# femtoBeacon_PRO_r3_0_1_single_sided.net
KiCad netlist of a schematic drawn in EAGLE
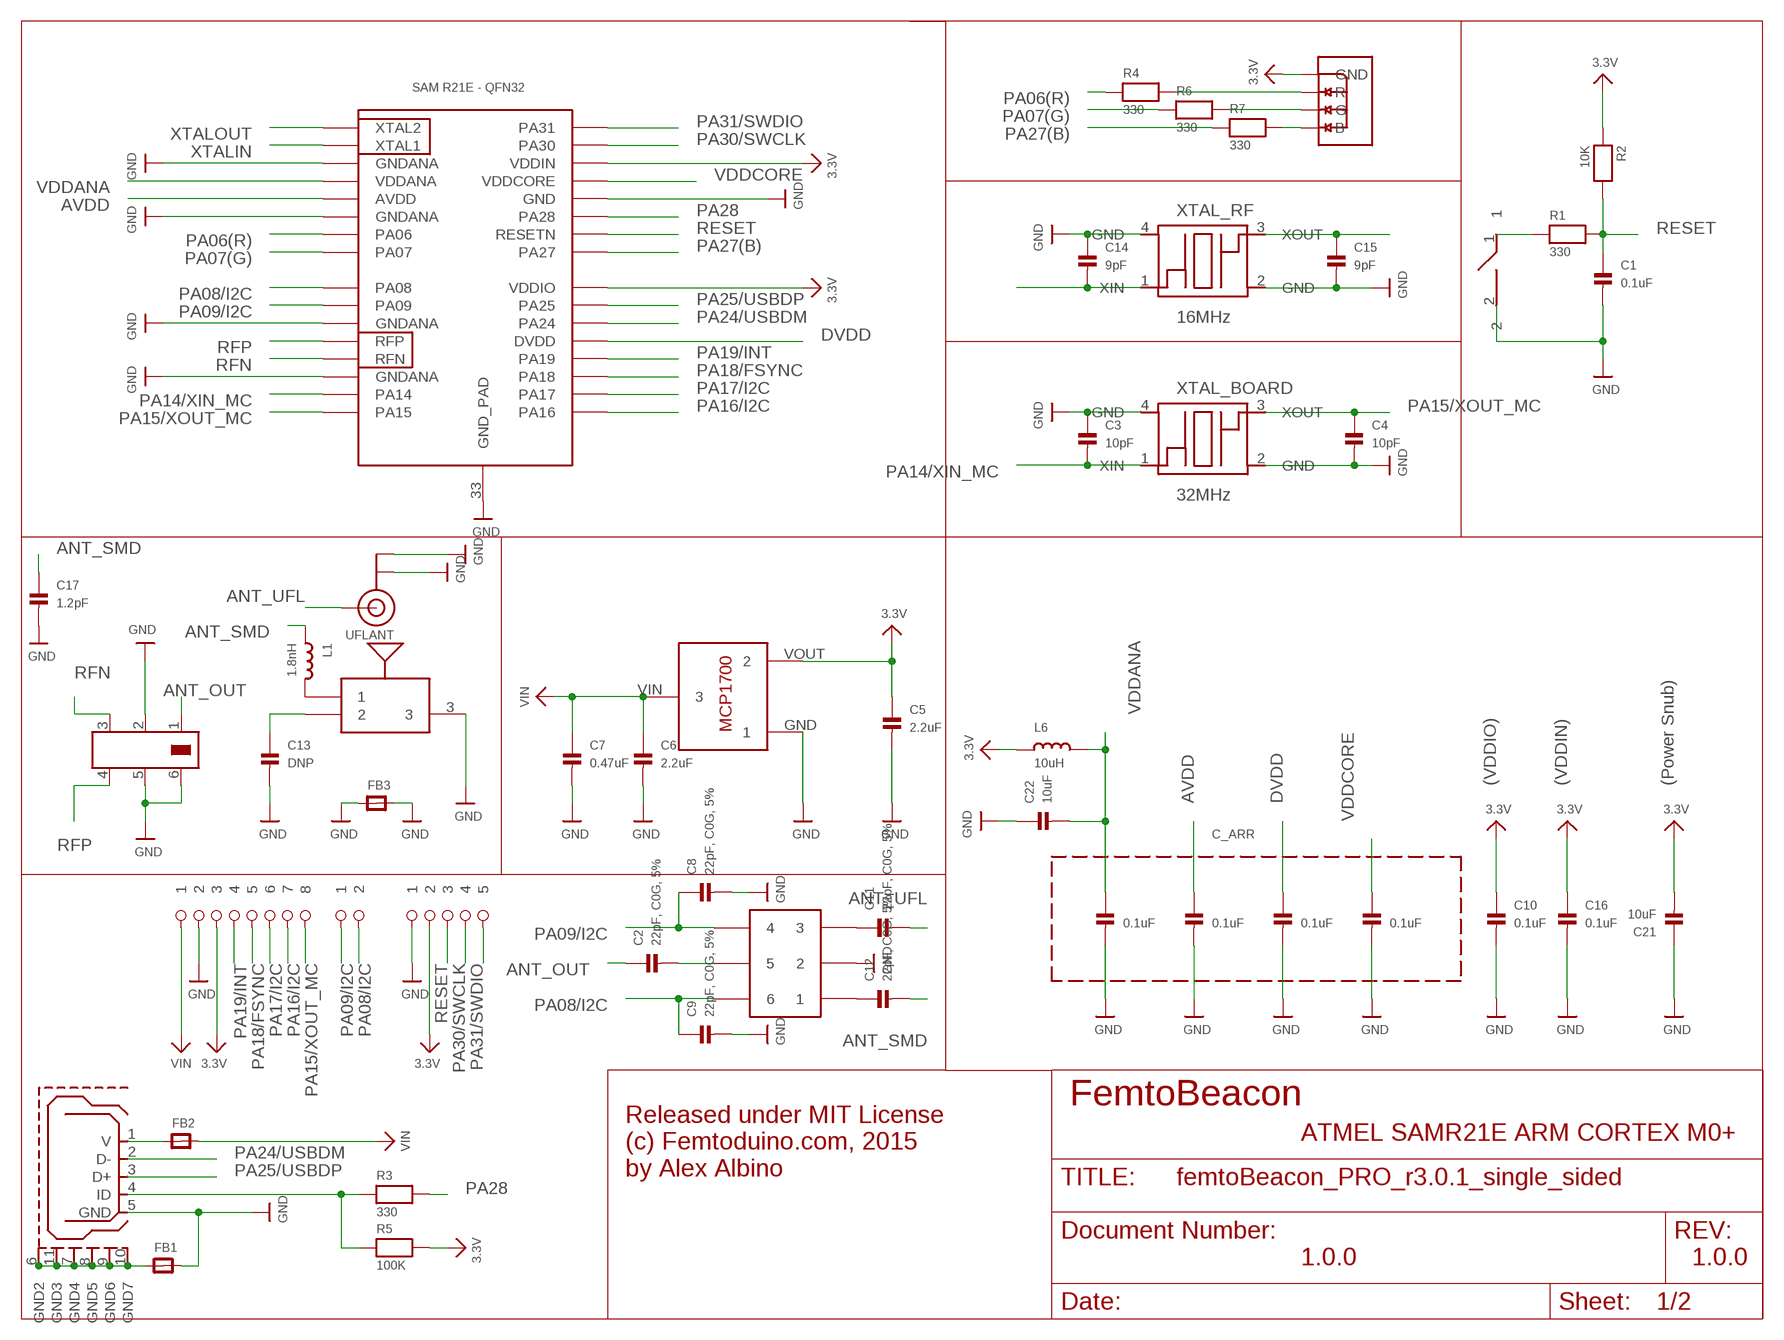
[diagram p0: schematic, sheet 1]
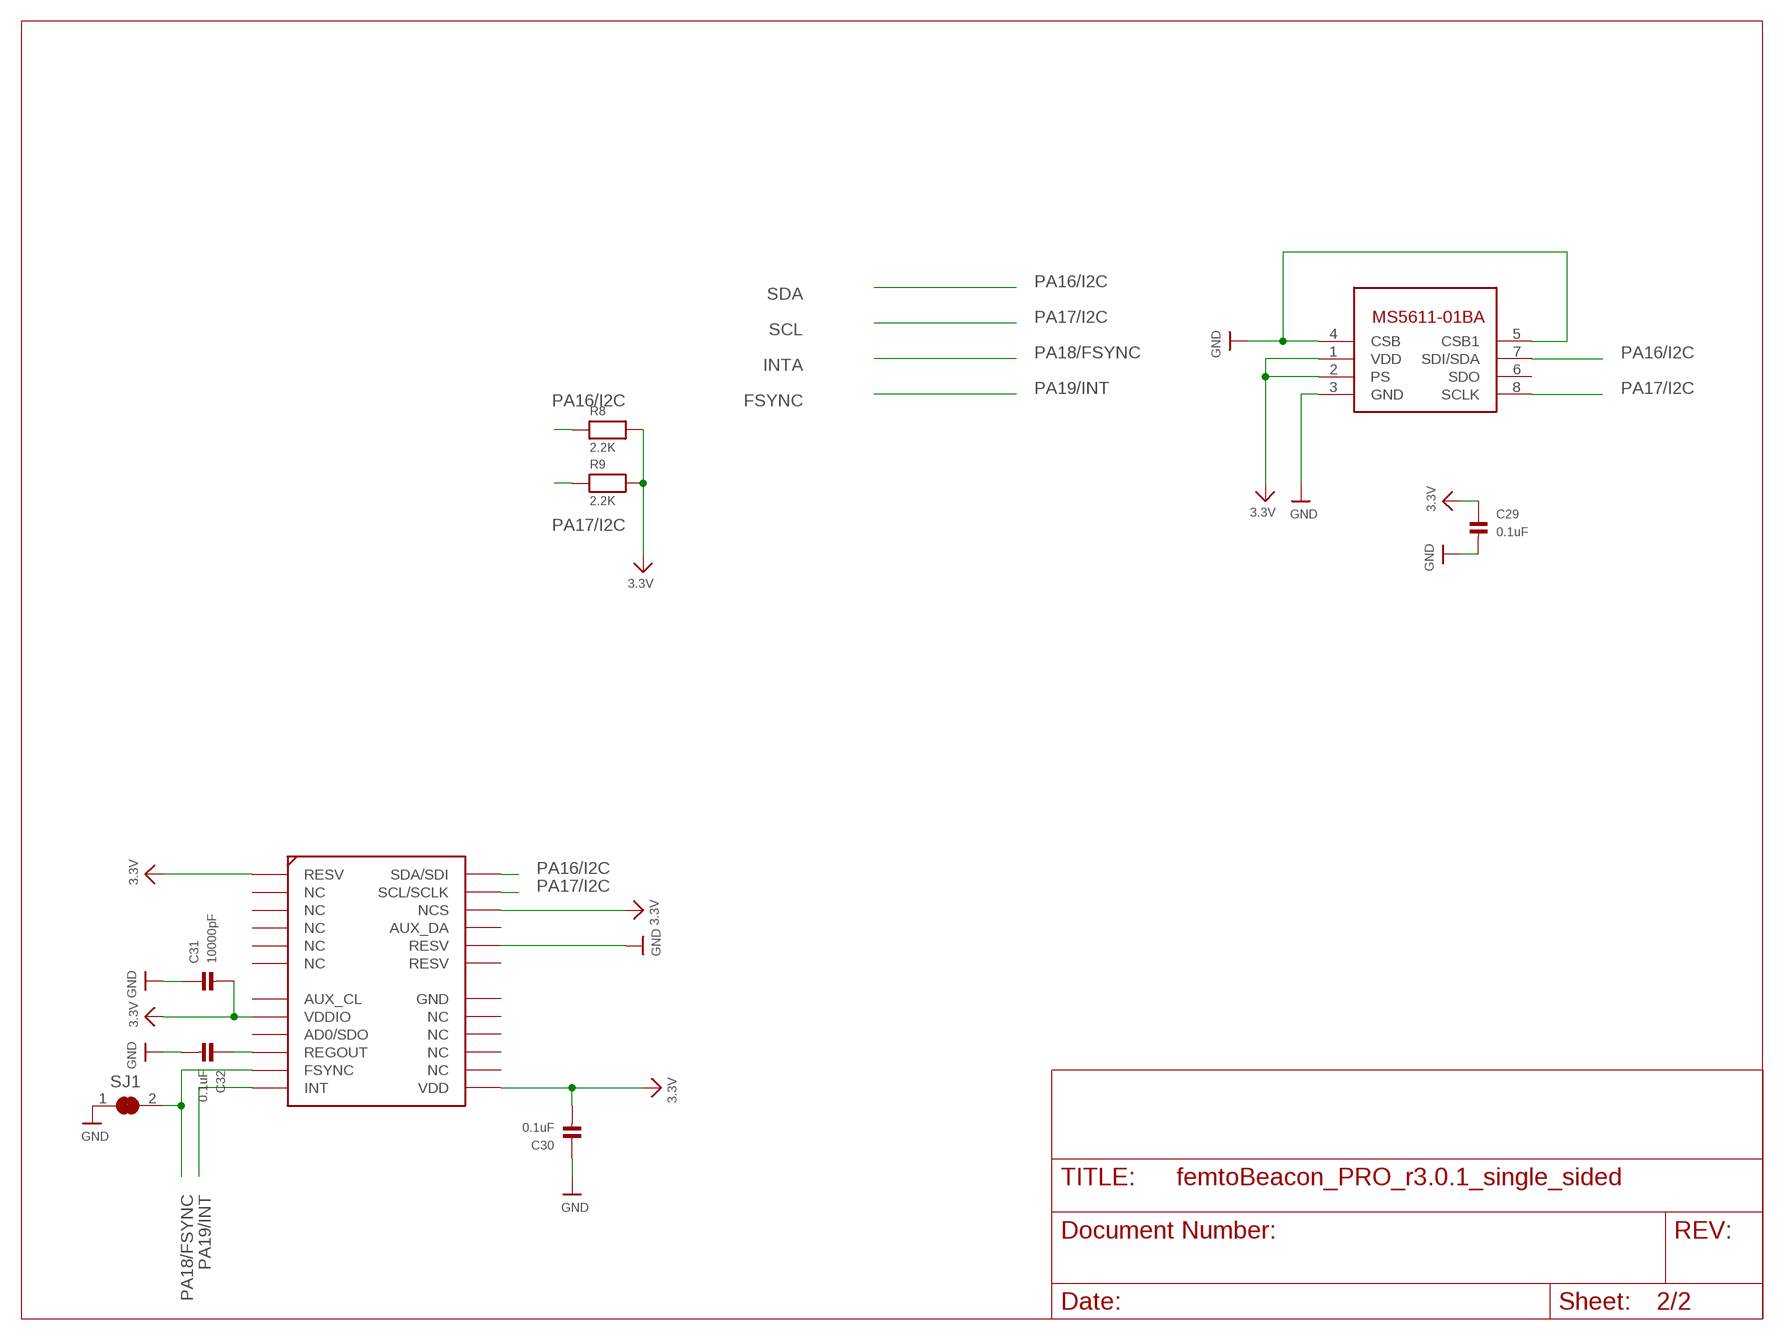
[diagram p1: schematic, sheet 2]

(export (version "E")
  (design (tool "Eeschema 10.0.6"))
  (components
    (comp (ref "BARO")
      (value "MS5611-01BA03")
      (footprint "eagle-import:MS5611-01BA03")
      (libsource (lib "eagle-import") (part "MS5611-01BA03"))
    )
    (comp (ref "C29")
      (value "0.1uF")
      (footprint "eagle-import:_0402MP")
      (fields (field (name "DIGIKEY_PART") "490-3194-1-ND"))
      (libsource (lib "eagle-import") (part "CAP_CERAMIC_0402MP"))
    )
    (comp (ref "C30")
      (value "0.1uF")
      (footprint "eagle-import:_0402MP")
      (fields (field (name "DIGIKEY_PART") "490-3194-1-ND"))
      (libsource (lib "eagle-import") (part "CAP_CERAMIC_0402MP"))
    )
    (comp (ref "C31")
      (value "10000pF")
      (footprint "eagle-import:_0402MP")
      (fields (field (name "DIGIKEY_PART") "490-3194-1-ND"))
      (libsource (lib "eagle-import") (part "CAP_CERAMIC_0402MP"))
    )
    (comp (ref "C32")
      (value "0.1uF")
      (footprint "eagle-import:_0402MP")
      (fields (field (name "DIGIKEY_PART") "490-3194-1-ND"))
      (libsource (lib "eagle-import") (part "CAP_CERAMIC_0402MP"))
    )
    (comp (ref "IMU")
      (value "MPU-9250")
      (footprint "eagle-import:QFN_3X3MM")
      (libsource (lib "eagle-import") (part "MPU-9250"))
    )
    (comp (ref "R8")
      (value "2.2K")
      (footprint "eagle-import:_0402MP")
      (libsource (lib "eagle-import") (part "RESISTOR_0402MP"))
    )
    (comp (ref "R9")
      (value "2.2K")
      (footprint "eagle-import:_0402MP")
      (libsource (lib "eagle-import") (part "RESISTOR_0402MP"))
    )
    (comp (ref "SJ1")
      (value "SOLDERJUMPER_CLOSED")
      (footprint "eagle-import:SOLDERJUMPER_CLOSEDWIRE")
      (libsource (lib "eagle-import") (part "SOLDERJUMPER_CLOSED"))
    )
    (comp (ref "ASWITCH")
      (value "AS222-92LF")
      (footprint "eagle-import:AS222-92LF")
      (libsource (lib "eagle-import") (part "AS222-92LF"))
    )
    (comp (ref "BALUN")
      (value "JOHANSON_2450BM15A0015E")
      (footprint "eagle-import:0805_BALUN")
      (libsource (lib "eagle-import") (part "JOHANSON_2450BM15A0015E"))
    )
    (comp (ref "BTN_RESET")
      (value "DNP")
      (footprint "eagle-import:SPST_SMD")
      (libsource (lib "eagle-import") (part "SPST_SMD"))
    )
    (comp (ref "C1")
      (value "0.1uF")
      (footprint "eagle-import:_0402MP")
      (fields (field (name "DIGIKEY_PART") "490-3194-1-ND"))
      (libsource (lib "eagle-import") (part "CAP_CERAMIC_0402MP"))
    )
    (comp (ref "C2")
      (value "22pF, C0G, 5%")
      (footprint "eagle-import:_0402MP")
      (fields (field (name "DIGIKEY_PART") "490-3194-1-ND"))
      (libsource (lib "eagle-import") (part "CAP_CERAMIC_0402MP"))
    )
    (comp (ref "C3")
      (value "10pF")
      (footprint "eagle-import:_0402MP")
      (fields (field (name "DIGIKEY_PART") "490-3194-1-ND"))
      (libsource (lib "eagle-import") (part "CAP_CERAMIC_0402MP"))
    )
    (comp (ref "C4")
      (value "10pF")
      (footprint "eagle-import:_0402MP")
      (fields (field (name "DIGIKEY_PART") "490-3194-1-ND"))
      (libsource (lib "eagle-import") (part "CAP_CERAMIC_0402MP"))
    )
    (comp (ref "C5")
      (value "2.2uF")
      (footprint "eagle-import:_0402MP")
      (libsource (lib "eagle-import") (part "CAP_CERAMIC_0402MP"))
    )
    (comp (ref "C6")
      (value "2.2uF")
      (footprint "eagle-import:_0402MP")
      (libsource (lib "eagle-import") (part "CAP_CERAMIC_0402MP"))
    )
    (comp (ref "C7")
      (value "0.47uF")
      (footprint "eagle-import:_0402MP")
      (libsource (lib "eagle-import") (part "CAP_CERAMIC_0402MP"))
    )
    (comp (ref "C8")
      (value "22pF, C0G, 5%")
      (footprint "eagle-import:_0402MP")
      (fields (field (name "DIGIKEY_PART") "490-3194-1-ND"))
      (libsource (lib "eagle-import") (part "CAP_CERAMIC_0402MP"))
    )
    (comp (ref "C9")
      (value "22pF, C0G, 5%")
      (footprint "eagle-import:_0402MP")
      (fields (field (name "DIGIKEY_PART") "490-3194-1-ND"))
      (libsource (lib "eagle-import") (part "CAP_CERAMIC_0402MP"))
    )
    (comp (ref "C10")
      (value "0.1uF")
      (footprint "eagle-import:_0402MP")
      (fields (field (name "DIGIKEY_PART") "490-3194-1-ND"))
      (libsource (lib "eagle-import") (part "CAP_CERAMIC_0402MP"))
    )
    (comp (ref "C11")
      (value "22pF, C0G, 5%")
      (footprint "eagle-import:_0402MP")
      (fields (field (name "DIGIKEY_PART") "490-3194-1-ND"))
      (libsource (lib "eagle-import") (part "CAP_CERAMIC_0402MP"))
    )
    (comp (ref "C12")
      (value "22pF, C0G, 5%")
      (footprint "eagle-import:_0402MP")
      (fields (field (name "DIGIKEY_PART") "490-3194-1-ND"))
      (libsource (lib "eagle-import") (part "CAP_CERAMIC_0402MP"))
    )
    (comp (ref "C13")
      (value "DNP")
      (footprint "eagle-import:_0402MP")
      (fields (field (name "DIGIKEY_PART") "490-3194-1-ND"))
      (libsource (lib "eagle-import") (part "CAP_CERAMIC_0402MP"))
    )
    (comp (ref "C14")
      (value "9pF")
      (footprint "eagle-import:_0402MP")
      (fields (field (name "DIGIKEY_PART") "490-3194-1-ND"))
      (libsource (lib "eagle-import") (part "CAP_CERAMIC_0402MP"))
    )
    (comp (ref "C15")
      (value "9pF")
      (footprint "eagle-import:_0402MP")
      (fields (field (name "DIGIKEY_PART") "490-3194-1-ND"))
      (libsource (lib "eagle-import") (part "CAP_CERAMIC_0402MP"))
    )
    (comp (ref "C16")
      (value "0.1uF")
      (footprint "eagle-import:_0402MP")
      (fields (field (name "DIGIKEY_PART") "490-3194-1-ND"))
      (libsource (lib "eagle-import") (part "CAP_CERAMIC_0402MP"))
    )
    (comp (ref "C17")
      (value "1.2pF")
      (footprint "eagle-import:_0402MP")
      (libsource (lib "eagle-import") (part "CAP_CERAMIC_0402MP"))
    )
    (comp (ref "C21")
      (value "10uF")
      (footprint "eagle-import:_0402MP")
      (libsource (lib "eagle-import") (part "CAP_CERAMIC_0402MP"))
    )
    (comp (ref "C22")
      (value "10uF")
      (footprint "eagle-import:_0402MP")
      (libsource (lib "eagle-import") (part "CAP_CERAMIC_0402MP"))
    )
    (comp (ref "C_ARR")
      (value "0.1uF")
      (footprint "eagle-import:CAPACITOR_ARRAY_1206_MONO_1X4")
      (libsource (lib "eagle-import") (part "KEMET_CERAMIC_CAPACITOR_ARRAY_1X4"))
    )
    (comp (ref "FB1")
      (value "FERRITE_0603MP")
      (footprint "eagle-import:_0603MP")
      (libsource (lib "eagle-import") (part "FERRITE_0603MP"))
    )
    (comp (ref "FB2")
      (value "FERRITE_0603MP")
      (footprint "eagle-import:_0603MP")
      (libsource (lib "eagle-import") (part "FERRITE_0603MP"))
    )
    (comp (ref "FB3")
      (value "FERRITE_0603MP")
      (footprint "eagle-import:_0603MP")
      (libsource (lib "eagle-import") (part "FERRITE_0603MP"))
    )
    (comp (ref "IC")
      (value "ATSAMR21E18A-MUT")
      (footprint "eagle-import:QFN32")
      (libsource (lib "eagle-import") (part "ATSAMR21E18A-MUT"))
    )
    (comp (ref "L1")
      (value "1.8nH")
      (footprint "eagle-import:_0603MP")
      (libsource (lib "eagle-import") (part "INDUCTOR_0603MP"))
    )
    (comp (ref "L6")
      (value "10uH")
      (footprint "eagle-import:_0603MP")
      (libsource (lib "eagle-import") (part "INDUCTOR_0603MP"))
    )
    (comp (ref "LDO_VREG")
      (value "MCP1700T-3302E/TT")
      (footprint "eagle-import:MCP1700T-3302E_TT")
      (libsource (lib "eagle-import") (part "MCP1700T-3302E/TT"))
    )
    (comp (ref "R1")
      (value "330")
      (footprint "eagle-import:_0402MP")
      (libsource (lib "eagle-import") (part "RESISTOR_0402MP"))
    )
    (comp (ref "R2")
      (value "10K")
      (footprint "eagle-import:_0402MP")
      (libsource (lib "eagle-import") (part "RESISTOR_0402MP"))
    )
    (comp (ref "R3")
      (value "330")
      (footprint "eagle-import:_0402MP")
      (libsource (lib "eagle-import") (part "RESISTOR_0402MP"))
    )
    (comp (ref "R4")
      (value "330")
      (footprint "eagle-import:_0402MP")
      (libsource (lib "eagle-import") (part "RESISTOR_0402MP"))
    )
    (comp (ref "R5")
      (value "100K")
      (footprint "eagle-import:_0402MP")
      (libsource (lib "eagle-import") (part "RESISTOR_0402MP"))
    )
    (comp (ref "R6")
      (value "330")
      (footprint "eagle-import:_0402MP")
      (libsource (lib "eagle-import") (part "RESISTOR_0402MP"))
    )
    (comp (ref "R7")
      (value "330")
      (footprint "eagle-import:_0402MP")
      (libsource (lib "eagle-import") (part "RESISTOR_0402MP"))
    )
    (comp (ref "RGBLED")
      (value "LRTB_R48G")
      (footprint "eagle-import:LRTB_R48G")
      (libsource (lib "eagle-import") (part "LRTB_R48G"))
    )
    (comp (ref "SMDANT")
      (value "PULSE_ANT_2.4GHZ")
      (footprint "eagle-import:ANT_BAR")
      (libsource (lib "eagle-import") (part "PULSE_ANT_2.4GHZ"))
    )
    (comp (ref "U$5")
      (value "1X8_ROUND")
      (footprint "eagle-import:1X8_ROUND")
      (libsource (lib "eagle-import") (part "1X8_ROUND"))
    )
    (comp (ref "U$9")
      (value "1X2_ROUND")
      (footprint "eagle-import:1X2_ROUND")
      (libsource (lib "eagle-import") (part "1X2_ROUND"))
    )
    (comp (ref "U$10")
      (value "1X5_ROUND")
      (footprint "eagle-import:1X5_ROUND")
      (libsource (lib "eagle-import") (part "1X5_ROUND"))
    )
    (comp (ref "UFLANT")
      (value "ANTENNA_U.FL")
      (footprint "eagle-import:U.FL")
      (libsource (lib "eagle-import") (part "ANTENNA_U.FL"))
    )
    (comp (ref "USB")
      (value "USB_MICROB")
      (footprint "eagle-import:USB_MICROB_PACKAGE")
      (libsource (lib "eagle-import") (part "USB_MICROB"))
    )
    (comp (ref "XTAL_BOARD")
      (value "32MHz")
      (footprint "eagle-import:FA-128")
      (libsource (lib "eagle-import") (part "FA-128"))
    )
    (comp (ref "XTAL_RF")
      (value "16MHz")
      (footprint "eagle-import:TSX-3225")
      (libsource (lib "eagle-import") (part "TSX-3225"))
    )
  )
  (nets
    (net (code "1") (name "3.3V") (class "Default")
      (node (ref "BARO") (pin "1") (pinfunction "VDD_1") (pintype "bidirectional"))
      (node (ref "BARO") (pin "2") (pinfunction "PS_2") (pintype "bidirectional"))
      (node (ref "C10") (pin "1") (pinfunction "P$1_1") (pintype "passive"))
      (node (ref "C16") (pin "1") (pinfunction "P$1_1") (pintype "passive"))
      (node (ref "C21") (pin "2") (pinfunction "P$2_2") (pintype "passive"))
      (node (ref "C29") (pin "1") (pinfunction "P$1_1") (pintype "passive"))
      (node (ref "C30") (pin "2") (pinfunction "P$2_2") (pintype "passive"))
      (node (ref "C31") (pin "2") (pinfunction "P$2_2") (pintype "passive"))
      (node (ref "C5") (pin "1") (pinfunction "P$1_1") (pintype "passive"))
      (node (ref "IC") (pin "24") (pinfunction "VDDIO_24") (pintype "bidirectional"))
      (node (ref "IC") (pin "30") (pinfunction "VDDIN_30") (pintype "bidirectional"))
      (node (ref "IMU") (pin "P$1") (pinfunction "RESV_P$1") (pintype "bidirectional"))
      (node (ref "IMU") (pin "P$13") (pinfunction "VDD_P$13") (pintype "bidirectional"))
      (node (ref "IMU") (pin "P$22") (pinfunction "NCS_P$22") (pintype "bidirectional"))
      (node (ref "IMU") (pin "P$8") (pinfunction "VDDIO_P$8") (pintype "bidirectional"))
      (node (ref "L6") (pin "1") (pinfunction "1_1") (pintype "passive"))
      (node (ref "LDO_VREG") (pin "VOUT") (pinfunction "2_VOUT") (pintype "bidirectional"))
      (node (ref "R2") (pin "1") (pinfunction "1_1") (pintype "passive"))
      (node (ref "R5") (pin "2") (pinfunction "2_2") (pintype "passive"))
      (node (ref "R8") (pin "2") (pinfunction "2_2") (pintype "passive"))
      (node (ref "R9") (pin "2") (pinfunction "2_2") (pintype "passive"))
      (node (ref "RGBLED") (pin "1") (pinfunction "GND_1") (pintype "bidirectional"))
      (node (ref "U$10") (pin "P$2") (pinfunction "2_P$2") (pintype "bidirectional"))
      (node (ref "U$5") (pin "P$3") (pinfunction "3_P$3") (pintype "bidirectional"))
    )
    (net (code "2") (name "ANT_OUT") (class "Default")
      (node (ref "BALUN") (pin "1") (pinfunction "1_1") (pintype "bidirectional"))
      (node (ref "C2") (pin "1") (pinfunction "P$1_1") (pintype "passive"))
    )
    (net (code "3") (name "ANT_SMD") (class "Default")
      (node (ref "C12") (pin "2") (pinfunction "P$2_2") (pintype "passive"))
      (node (ref "C17") (pin "1") (pinfunction "P$1_1") (pintype "passive"))
      (node (ref "L1") (pin "1") (pinfunction "1_1") (pintype "passive"))
    )
    (net (code "4") (name "ANT_UFL") (class "Default")
      (node (ref "C11") (pin "2") (pinfunction "P$2_2") (pintype "passive"))
      (node (ref "UFLANT") (pin "3") (pinfunction "SIGNAL_3") (pintype "passive"))
    )
    (net (code "5") (name "AVDD") (class "Default")
      (node (ref "C_ARR") (pin "3") (pinfunction "P$3_3") (pintype "passive"))
      (node (ref "IC") (pin "5") (pinfunction "AVDD_5") (pintype "bidirectional"))
    )
    (net (code "6") (name "DVDD") (class "Default")
      (node (ref "C_ARR") (pin "5") (pinfunction "P$5_5") (pintype "passive"))
      (node (ref "IC") (pin "21") (pinfunction "DVDD_21") (pintype "bidirectional"))
    )
    (net (code "7") (name "GND") (class "Default")
      (node (ref "ASWITCH") (pin "PIN2") (pinfunction "2_PIN2") (pintype "bidirectional"))
      (node (ref "BALUN") (pin "2") (pinfunction "2_2") (pintype "bidirectional"))
      (node (ref "BALUN") (pin "5") (pinfunction "5_5") (pintype "bidirectional"))
      (node (ref "BALUN") (pin "6") (pinfunction "6_6") (pintype "bidirectional"))
      (node (ref "BARO") (pin "3") (pinfunction "GND_3") (pintype "bidirectional"))
      (node (ref "BARO") (pin "4") (pinfunction "CSB_4") (pintype "bidirectional"))
      (node (ref "BARO") (pin "5") (pinfunction "CSB1_5") (pintype "bidirectional"))
      (node (ref "BTN_RESET") (pin "2") (pinfunction "2_2") (pintype "bidirectional"))
      (node (ref "C1") (pin "2") (pinfunction "P$2_2") (pintype "passive"))
      (node (ref "C10") (pin "2") (pinfunction "P$2_2") (pintype "passive"))
      (node (ref "C13") (pin "2") (pinfunction "P$2_2") (pintype "passive"))
      (node (ref "C14") (pin "1") (pinfunction "P$1_1") (pintype "passive"))
      (node (ref "C15") (pin "2") (pinfunction "P$2_2") (pintype "passive"))
      (node (ref "C16") (pin "2") (pinfunction "P$2_2") (pintype "passive"))
      (node (ref "C17") (pin "2") (pinfunction "P$2_2") (pintype "passive"))
      (node (ref "C21") (pin "1") (pinfunction "P$1_1") (pintype "passive"))
      (node (ref "C22") (pin "1") (pinfunction "P$1_1") (pintype "passive"))
      (node (ref "C29") (pin "2") (pinfunction "P$2_2") (pintype "passive"))
      (node (ref "C3") (pin "1") (pinfunction "P$1_1") (pintype "passive"))
      (node (ref "C30") (pin "1") (pinfunction "P$1_1") (pintype "passive"))
      (node (ref "C31") (pin "1") (pinfunction "P$1_1") (pintype "passive"))
      (node (ref "C32") (pin "2") (pinfunction "P$2_2") (pintype "passive"))
      (node (ref "C4") (pin "2") (pinfunction "P$2_2") (pintype "passive"))
      (node (ref "C5") (pin "2") (pinfunction "P$2_2") (pintype "passive"))
      (node (ref "C6") (pin "2") (pinfunction "P$2_2") (pintype "passive"))
      (node (ref "C7") (pin "2") (pinfunction "P$2_2") (pintype "passive"))
      (node (ref "C8") (pin "2") (pinfunction "P$2_2") (pintype "passive"))
      (node (ref "C9") (pin "2") (pinfunction "P$2_2") (pintype "passive"))
      (node (ref "C_ARR") (pin "2") (pinfunction "P$2_2") (pintype "passive"))
      (node (ref "C_ARR") (pin "4") (pinfunction "P$4_4") (pintype "passive"))
      (node (ref "C_ARR") (pin "6") (pinfunction "P$6_6") (pintype "passive"))
      (node (ref "C_ARR") (pin "8") (pinfunction "P$8_8") (pintype "passive"))
      (node (ref "FB1") (pin "2") (pinfunction "P$2_2") (pintype "passive"))
      (node (ref "FB3") (pin "1") (pinfunction "P$1_1") (pintype "passive"))
      (node (ref "FB3") (pin "2") (pinfunction "P$2_2") (pintype "passive"))
      (node (ref "IC") (pin "11") (pinfunction "GNDANA_11") (pintype "bidirectional"))
      (node (ref "IC") (pin "14") (pinfunction "GNDANA_14") (pintype "bidirectional"))
      (node (ref "IC") (pin "28") (pinfunction "GND_28") (pintype "bidirectional"))
      (node (ref "IC") (pin "3") (pinfunction "GNDANA_3") (pintype "bidirectional"))
      (node (ref "IC") (pin "33") (pinfunction "GND_PAD_33") (pintype "bidirectional"))
      (node (ref "IC") (pin "6") (pinfunction "GNDANA_6") (pintype "bidirectional"))
      (node (ref "IMU") (pin "P$20") (pinfunction "RESV_P$20") (pintype "bidirectional"))
      (node (ref "LDO_VREG") (pin "GND") (pinfunction "1_GND") (pintype "bidirectional"))
      (node (ref "SJ1") (pin "1") (pinfunction "1_1") (pintype "passive"))
      (node (ref "SMDANT") (pin "3") (pinfunction "3_3") (pintype "bidirectional"))
      (node (ref "U$10") (pin "P$1") (pinfunction "1_P$1") (pintype "bidirectional"))
      (node (ref "U$5") (pin "P$2") (pinfunction "2_P$2") (pintype "bidirectional"))
      (node (ref "UFLANT") (pin "1") (pinfunction "GND_1") (pintype "passive"))
      (node (ref "UFLANT") (pin "2") (pinfunction "GND_2") (pintype "passive"))
      (node (ref "USB") (pin "5") (pinfunction "GND_5") (pintype "bidirectional"))
      (node (ref "XTAL_BOARD") (pin "2") (pinfunction "GND_2") (pintype "bidirectional"))
      (node (ref "XTAL_BOARD") (pin "4") (pinfunction "GND_4") (pintype "bidirectional"))
      (node (ref "XTAL_RF") (pin "2") (pinfunction "GND_2") (pintype "bidirectional"))
      (node (ref "XTAL_RF") (pin "4") (pinfunction "GND_4") (pintype "bidirectional"))
    )
    (net (code "8") (name "Net-(ASWITCH-1)") (class "Default")
      (node (ref "ASWITCH") (pin "PIN1") (pinfunction "1_PIN1") (pintype "bidirectional"))
      (node (ref "C12") (pin "1") (pinfunction "P$1_1") (pintype "passive"))
    )
    (net (code "9") (name "Net-(ASWITCH-3)") (class "Default")
      (node (ref "ASWITCH") (pin "PIN3") (pinfunction "3_PIN3") (pintype "bidirectional"))
      (node (ref "C11") (pin "1") (pinfunction "P$1_1") (pintype "passive"))
    )
    (net (code "10") (name "Net-(ASWITCH-5)") (class "Default")
      (node (ref "ASWITCH") (pin "PIN5") (pinfunction "5_PIN5") (pintype "bidirectional"))
      (node (ref "C2") (pin "2") (pinfunction "P$2_2") (pintype "passive"))
    )
    (net (code "11") (name "Net-(BTN_RESET-Pad1)") (class "Default")
      (node (ref "BTN_RESET") (pin "1") (pinfunction "1_1") (pintype "bidirectional"))
      (node (ref "R1") (pin "1") (pinfunction "1_1") (pintype "passive"))
    )
    (net (code "12") (name "Net-(C13-P$1)") (class "Default")
      (node (ref "C13") (pin "1") (pinfunction "P$1_1") (pintype "passive"))
      (node (ref "SMDANT") (pin "2") (pinfunction "2_2") (pintype "bidirectional"))
    )
    (net (code "13") (name "Net-(C32-P$1)") (class "Default")
      (node (ref "C32") (pin "1") (pinfunction "P$1_1") (pintype "passive"))
      (node (ref "IMU") (pin "P$10") (pinfunction "REGOUT_P$10") (pintype "bidirectional"))
    )
    (net (code "14") (name "Net-(FB1-P$1)") (class "Default")
      (node (ref "FB1") (pin "1") (pinfunction "P$1_1") (pintype "passive"))
      (node (ref "USB") (pin "10") (pinfunction "GND7_10") (pintype "bidirectional"))
      (node (ref "USB") (pin "11") (pinfunction "GND3_11") (pintype "bidirectional"))
      (node (ref "USB") (pin "6") (pinfunction "GND2_6") (pintype "bidirectional"))
      (node (ref "USB") (pin "7") (pinfunction "GND4_7") (pintype "bidirectional"))
      (node (ref "USB") (pin "8") (pinfunction "GND5_8") (pintype "bidirectional"))
      (node (ref "USB") (pin "9") (pinfunction "GND6_9") (pintype "bidirectional"))
    )
    (net (code "15") (name "Net-(FB2-P$1)") (class "Default")
      (node (ref "FB2") (pin "1") (pinfunction "P$1_1") (pintype "passive"))
      (node (ref "USB") (pin "1") (pinfunction "V_1") (pintype "bidirectional"))
    )
    (net (code "16") (name "Net-(L1-Pad2)") (class "Default")
      (node (ref "L1") (pin "2") (pinfunction "2_2") (pintype "passive"))
      (node (ref "SMDANT") (pin "1") (pinfunction "1_1") (pintype "bidirectional"))
    )
    (net (code "17") (name "Net-(RGBLED-B)") (class "Default")
      (node (ref "R7") (pin "2") (pinfunction "2_2") (pintype "passive"))
      (node (ref "RGBLED") (pin "4") (pinfunction "B_4") (pintype "bidirectional"))
    )
    (net (code "18") (name "Net-(RGBLED-G)") (class "Default")
      (node (ref "R6") (pin "2") (pinfunction "2_2") (pintype "passive"))
      (node (ref "RGBLED") (pin "3") (pinfunction "G_3") (pintype "bidirectional"))
    )
    (net (code "19") (name "Net-(RGBLED-R)") (class "Default")
      (node (ref "R4") (pin "2") (pinfunction "2_2") (pintype "passive"))
      (node (ref "RGBLED") (pin "2") (pinfunction "R_2") (pintype "bidirectional"))
    )
    (net (code "20") (name "Net-(USB-ID)") (class "Default")
      (node (ref "R3") (pin "1") (pinfunction "1_1") (pintype "passive"))
      (node (ref "R5") (pin "1") (pinfunction "1_1") (pintype "passive"))
      (node (ref "USB") (pin "4") (pinfunction "ID_4") (pintype "bidirectional"))
    )
    (net (code "21") (name "PA06(R)") (class "Default")
      (node (ref "IC") (pin "7") (pinfunction "PA06_7") (pintype "bidirectional"))
      (node (ref "R4") (pin "1") (pinfunction "1_1") (pintype "passive"))
    )
    (net (code "22") (name "PA07(G)") (class "Default")
      (node (ref "IC") (pin "8") (pinfunction "PA07_8") (pintype "bidirectional"))
      (node (ref "R6") (pin "1") (pinfunction "1_1") (pintype "passive"))
    )
    (net (code "23") (name "PA08{slash}I2C") (class "Default")
      (node (ref "ASWITCH") (pin "PIN6") (pinfunction "6_PIN6") (pintype "bidirectional"))
      (node (ref "C9") (pin "1") (pinfunction "P$1_1") (pintype "passive"))
      (node (ref "IC") (pin "9") (pinfunction "PA08_9") (pintype "bidirectional"))
      (node (ref "U$9") (pin "P$2") (pinfunction "2_P$2") (pintype "bidirectional"))
    )
    (net (code "24") (name "PA09{slash}I2C") (class "Default")
      (node (ref "ASWITCH") (pin "PIN4") (pinfunction "4_PIN4") (pintype "bidirectional"))
      (node (ref "C8") (pin "1") (pinfunction "P$1_1") (pintype "passive"))
      (node (ref "IC") (pin "10") (pinfunction "PA09_10") (pintype "bidirectional"))
      (node (ref "U$9") (pin "P$1") (pinfunction "1_P$1") (pintype "bidirectional"))
    )
    (net (code "25") (name "PA14{slash}XIN_MC") (class "Default")
      (node (ref "C3") (pin "2") (pinfunction "P$2_2") (pintype "passive"))
      (node (ref "IC") (pin "15") (pinfunction "PA14_15") (pintype "bidirectional"))
      (node (ref "XTAL_BOARD") (pin "1") (pinfunction "XIN_1") (pintype "bidirectional"))
    )
    (net (code "26") (name "PA15{slash}XOUT_MC") (class "Default")
      (node (ref "C4") (pin "1") (pinfunction "P$1_1") (pintype "passive"))
      (node (ref "IC") (pin "16") (pinfunction "PA15_16") (pintype "bidirectional"))
      (node (ref "U$5") (pin "P$8") (pinfunction "8_P$8") (pintype "bidirectional"))
      (node (ref "XTAL_BOARD") (pin "3") (pinfunction "XOUT_3") (pintype "bidirectional"))
    )
    (net (code "27") (name "PA16{slash}I2C") (class "Default")
      (node (ref "BARO") (pin "7") (pinfunction "SDI/SDA_7") (pintype "bidirectional"))
      (node (ref "IC") (pin "17") (pinfunction "PA16_17") (pintype "bidirectional"))
      (node (ref "IMU") (pin "P$24") (pinfunction "SDA/SDI_P$24") (pintype "bidirectional"))
      (node (ref "R8") (pin "1") (pinfunction "1_1") (pintype "passive"))
      (node (ref "U$5") (pin "P$7") (pinfunction "7_P$7") (pintype "bidirectional"))
    )
    (net (code "28") (name "PA17{slash}I2C") (class "Default")
      (node (ref "BARO") (pin "8") (pinfunction "SCLK_8") (pintype "bidirectional"))
      (node (ref "IC") (pin "18") (pinfunction "PA17_18") (pintype "bidirectional"))
      (node (ref "IMU") (pin "P$23") (pinfunction "SCL/SCLK_P$23") (pintype "bidirectional"))
      (node (ref "R9") (pin "1") (pinfunction "1_1") (pintype "passive"))
      (node (ref "U$5") (pin "P$6") (pinfunction "6_P$6") (pintype "bidirectional"))
    )
    (net (code "29") (name "PA18{slash}FSYNC") (class "Default")
      (node (ref "IC") (pin "19") (pinfunction "PA18_19") (pintype "bidirectional"))
      (node (ref "IMU") (pin "P$11") (pinfunction "FSYNC_P$11") (pintype "bidirectional"))
      (node (ref "SJ1") (pin "2") (pinfunction "2_2") (pintype "passive"))
      (node (ref "U$5") (pin "P$5") (pinfunction "5_P$5") (pintype "bidirectional"))
    )
    (net (code "30") (name "PA19{slash}INT") (class "Default")
      (node (ref "IC") (pin "20") (pinfunction "PA19_20") (pintype "bidirectional"))
      (node (ref "IMU") (pin "P$12") (pinfunction "INT_P$12") (pintype "bidirectional"))
      (node (ref "U$5") (pin "P$4") (pinfunction "4_P$4") (pintype "bidirectional"))
    )
    (net (code "31") (name "PA24{slash}USBDM") (class "Default")
      (node (ref "IC") (pin "22") (pinfunction "PA24_22") (pintype "bidirectional"))
      (node (ref "USB") (pin "2") (pinfunction "D-_2") (pintype "bidirectional"))
    )
    (net (code "32") (name "PA25{slash}USBDP") (class "Default")
      (node (ref "IC") (pin "23") (pinfunction "PA25_23") (pintype "bidirectional"))
      (node (ref "USB") (pin "3") (pinfunction "D+_3") (pintype "bidirectional"))
    )
    (net (code "33") (name "PA27(B)") (class "Default")
      (node (ref "IC") (pin "25") (pinfunction "PA27_25") (pintype "bidirectional"))
      (node (ref "R7") (pin "1") (pinfunction "1_1") (pintype "passive"))
    )
    (net (code "34") (name "PA28") (class "Default")
      (node (ref "IC") (pin "27") (pinfunction "PA28_27") (pintype "bidirectional"))
      (node (ref "R3") (pin "2") (pinfunction "2_2") (pintype "passive"))
    )
    (net (code "35") (name "PA30{slash}SWCLK") (class "Default")
      (node (ref "IC") (pin "31") (pinfunction "PA30_31") (pintype "bidirectional"))
      (node (ref "U$10") (pin "P$4") (pinfunction "4_P$4") (pintype "bidirectional"))
    )
    (net (code "36") (name "PA31{slash}SWDIO") (class "Default")
      (node (ref "IC") (pin "32") (pinfunction "PA31_32") (pintype "bidirectional"))
      (node (ref "U$10") (pin "P$5") (pinfunction "5_P$5") (pintype "bidirectional"))
    )
    (net (code "37") (name "RESET") (class "Default")
      (node (ref "C1") (pin "1") (pinfunction "P$1_1") (pintype "passive"))
      (node (ref "IC") (pin "26") (pinfunction "RESETN_26") (pintype "bidirectional"))
      (node (ref "R1") (pin "2") (pinfunction "2_2") (pintype "passive"))
      (node (ref "R2") (pin "2") (pinfunction "2_2") (pintype "passive"))
      (node (ref "U$10") (pin "P$3") (pinfunction "3_P$3") (pintype "bidirectional"))
    )
    (net (code "38") (name "RFN") (class "Default")
      (node (ref "BALUN") (pin "3") (pinfunction "3_3") (pintype "bidirectional"))
      (node (ref "IC") (pin "13") (pinfunction "RFN_13") (pintype "bidirectional"))
    )
    (net (code "39") (name "RFP") (class "Default")
      (node (ref "BALUN") (pin "4") (pinfunction "4_4") (pintype "bidirectional"))
      (node (ref "IC") (pin "12") (pinfunction "RFP_12") (pintype "bidirectional"))
    )
    (net (code "40") (name "VDDANA") (class "Default")
      (node (ref "C22") (pin "2") (pinfunction "P$2_2") (pintype "passive"))
      (node (ref "C_ARR") (pin "1") (pinfunction "P$1_1") (pintype "passive"))
      (node (ref "IC") (pin "4") (pinfunction "VDDANA_4") (pintype "bidirectional"))
      (node (ref "L6") (pin "2") (pinfunction "2_2") (pintype "passive"))
    )
    (net (code "41") (name "VDDCORE") (class "Default")
      (node (ref "C_ARR") (pin "7") (pinfunction "P$7_7") (pintype "passive"))
      (node (ref "IC") (pin "29") (pinfunction "VDDCORE_29") (pintype "bidirectional"))
    )
    (net (code "42") (name "VIN") (class "Default")
      (node (ref "C6") (pin "1") (pinfunction "P$1_1") (pintype "passive"))
      (node (ref "C7") (pin "1") (pinfunction "P$1_1") (pintype "passive"))
      (node (ref "FB2") (pin "2") (pinfunction "P$2_2") (pintype "passive"))
      (node (ref "LDO_VREG") (pin "VIN") (pinfunction "3_VIN") (pintype "bidirectional"))
      (node (ref "U$5") (pin "P$1") (pinfunction "1_P$1") (pintype "bidirectional"))
    )
    (net (code "43") (name "XTALIN") (class "Default")
      (node (ref "C14") (pin "2") (pinfunction "P$2_2") (pintype "passive"))
      (node (ref "IC") (pin "2") (pinfunction "XTAL1_2") (pintype "bidirectional"))
      (node (ref "XTAL_RF") (pin "1") (pinfunction "XIN_1") (pintype "bidirectional"))
    )
    (net (code "44") (name "XTALOUT") (class "Default")
      (node (ref "C15") (pin "1") (pinfunction "P$1_1") (pintype "passive"))
      (node (ref "IC") (pin "1") (pinfunction "XTAL2_1") (pintype "bidirectional"))
      (node (ref "XTAL_RF") (pin "3") (pinfunction "XOUT_3") (pintype "bidirectional"))
    )
    (net (code "45") (name "unconnected-(BARO-SDO-Pad6)") (class "Default")
      (node (ref "BARO") (pin "6") (pinfunction "SDO_6") (pintype "bidirectional"))
    )
    (net (code "46") (name "unconnected-(IMU-AD0{slash}SDO-PadP$9)") (class "Default")
      (node (ref "IMU") (pin "P$9") (pinfunction "AD0/SDO_P$9") (pintype "bidirectional"))
    )
    (net (code "47") (name "unconnected-(IMU-AUX_CL-PadP$7)") (class "Default")
      (node (ref "IMU") (pin "P$7") (pinfunction "AUX_CL_P$7") (pintype "bidirectional"))
    )
    (net (code "48") (name "unconnected-(IMU-AUX_DA-PadP$21)") (class "Default")
      (node (ref "IMU") (pin "P$21") (pinfunction "AUX_DA_P$21") (pintype "bidirectional"))
    )
    (net (code "49") (name "unconnected-(IMU-GND-PadP$18)") (class "Default")
      (node (ref "IMU") (pin "P$18") (pinfunction "GND_P$18") (pintype "bidirectional"))
    )
    (net (code "50") (name "unconnected-(IMU-NC-PadP$2)") (class "Default")
      (node (ref "IMU") (pin "P$2") (pinfunction "NC_P$2") (pintype "bidirectional"))
    )
    (net (code "51") (name "unconnected-(IMU-NC-PadP$3)") (class "Default")
      (node (ref "IMU") (pin "P$3") (pinfunction "NC_P$3") (pintype "bidirectional"))
    )
    (net (code "52") (name "unconnected-(IMU-NC-PadP$4)") (class "Default")
      (node (ref "IMU") (pin "P$4") (pinfunction "NC_P$4") (pintype "bidirectional"))
    )
    (net (code "53") (name "unconnected-(IMU-NC-PadP$5)") (class "Default")
      (node (ref "IMU") (pin "P$5") (pinfunction "NC_P$5") (pintype "bidirectional"))
    )
    (net (code "54") (name "unconnected-(IMU-NC-PadP$6)") (class "Default")
      (node (ref "IMU") (pin "P$6") (pinfunction "NC_P$6") (pintype "bidirectional"))
    )
    (net (code "55") (name "unconnected-(IMU-NC-PadP$14)") (class "Default")
      (node (ref "IMU") (pin "P$14") (pinfunction "NC_P$14") (pintype "bidirectional"))
    )
    (net (code "56") (name "unconnected-(IMU-NC-PadP$15)") (class "Default")
      (node (ref "IMU") (pin "P$15") (pinfunction "NC_P$15") (pintype "bidirectional"))
    )
    (net (code "57") (name "unconnected-(IMU-NC-PadP$16)") (class "Default")
      (node (ref "IMU") (pin "P$16") (pinfunction "NC_P$16") (pintype "bidirectional"))
    )
    (net (code "58") (name "unconnected-(IMU-NC-PadP$17)") (class "Default")
      (node (ref "IMU") (pin "P$17") (pinfunction "NC_P$17") (pintype "bidirectional"))
    )
    (net (code "59") (name "unconnected-(IMU-RESV-PadP$19)") (class "Default")
      (node (ref "IMU") (pin "P$19") (pinfunction "RESV_P$19") (pintype "bidirectional"))
    )
  )
)
